# HDMI_MicroUSB.net
KiCad netlist of a schematic drawn in Altium Designer
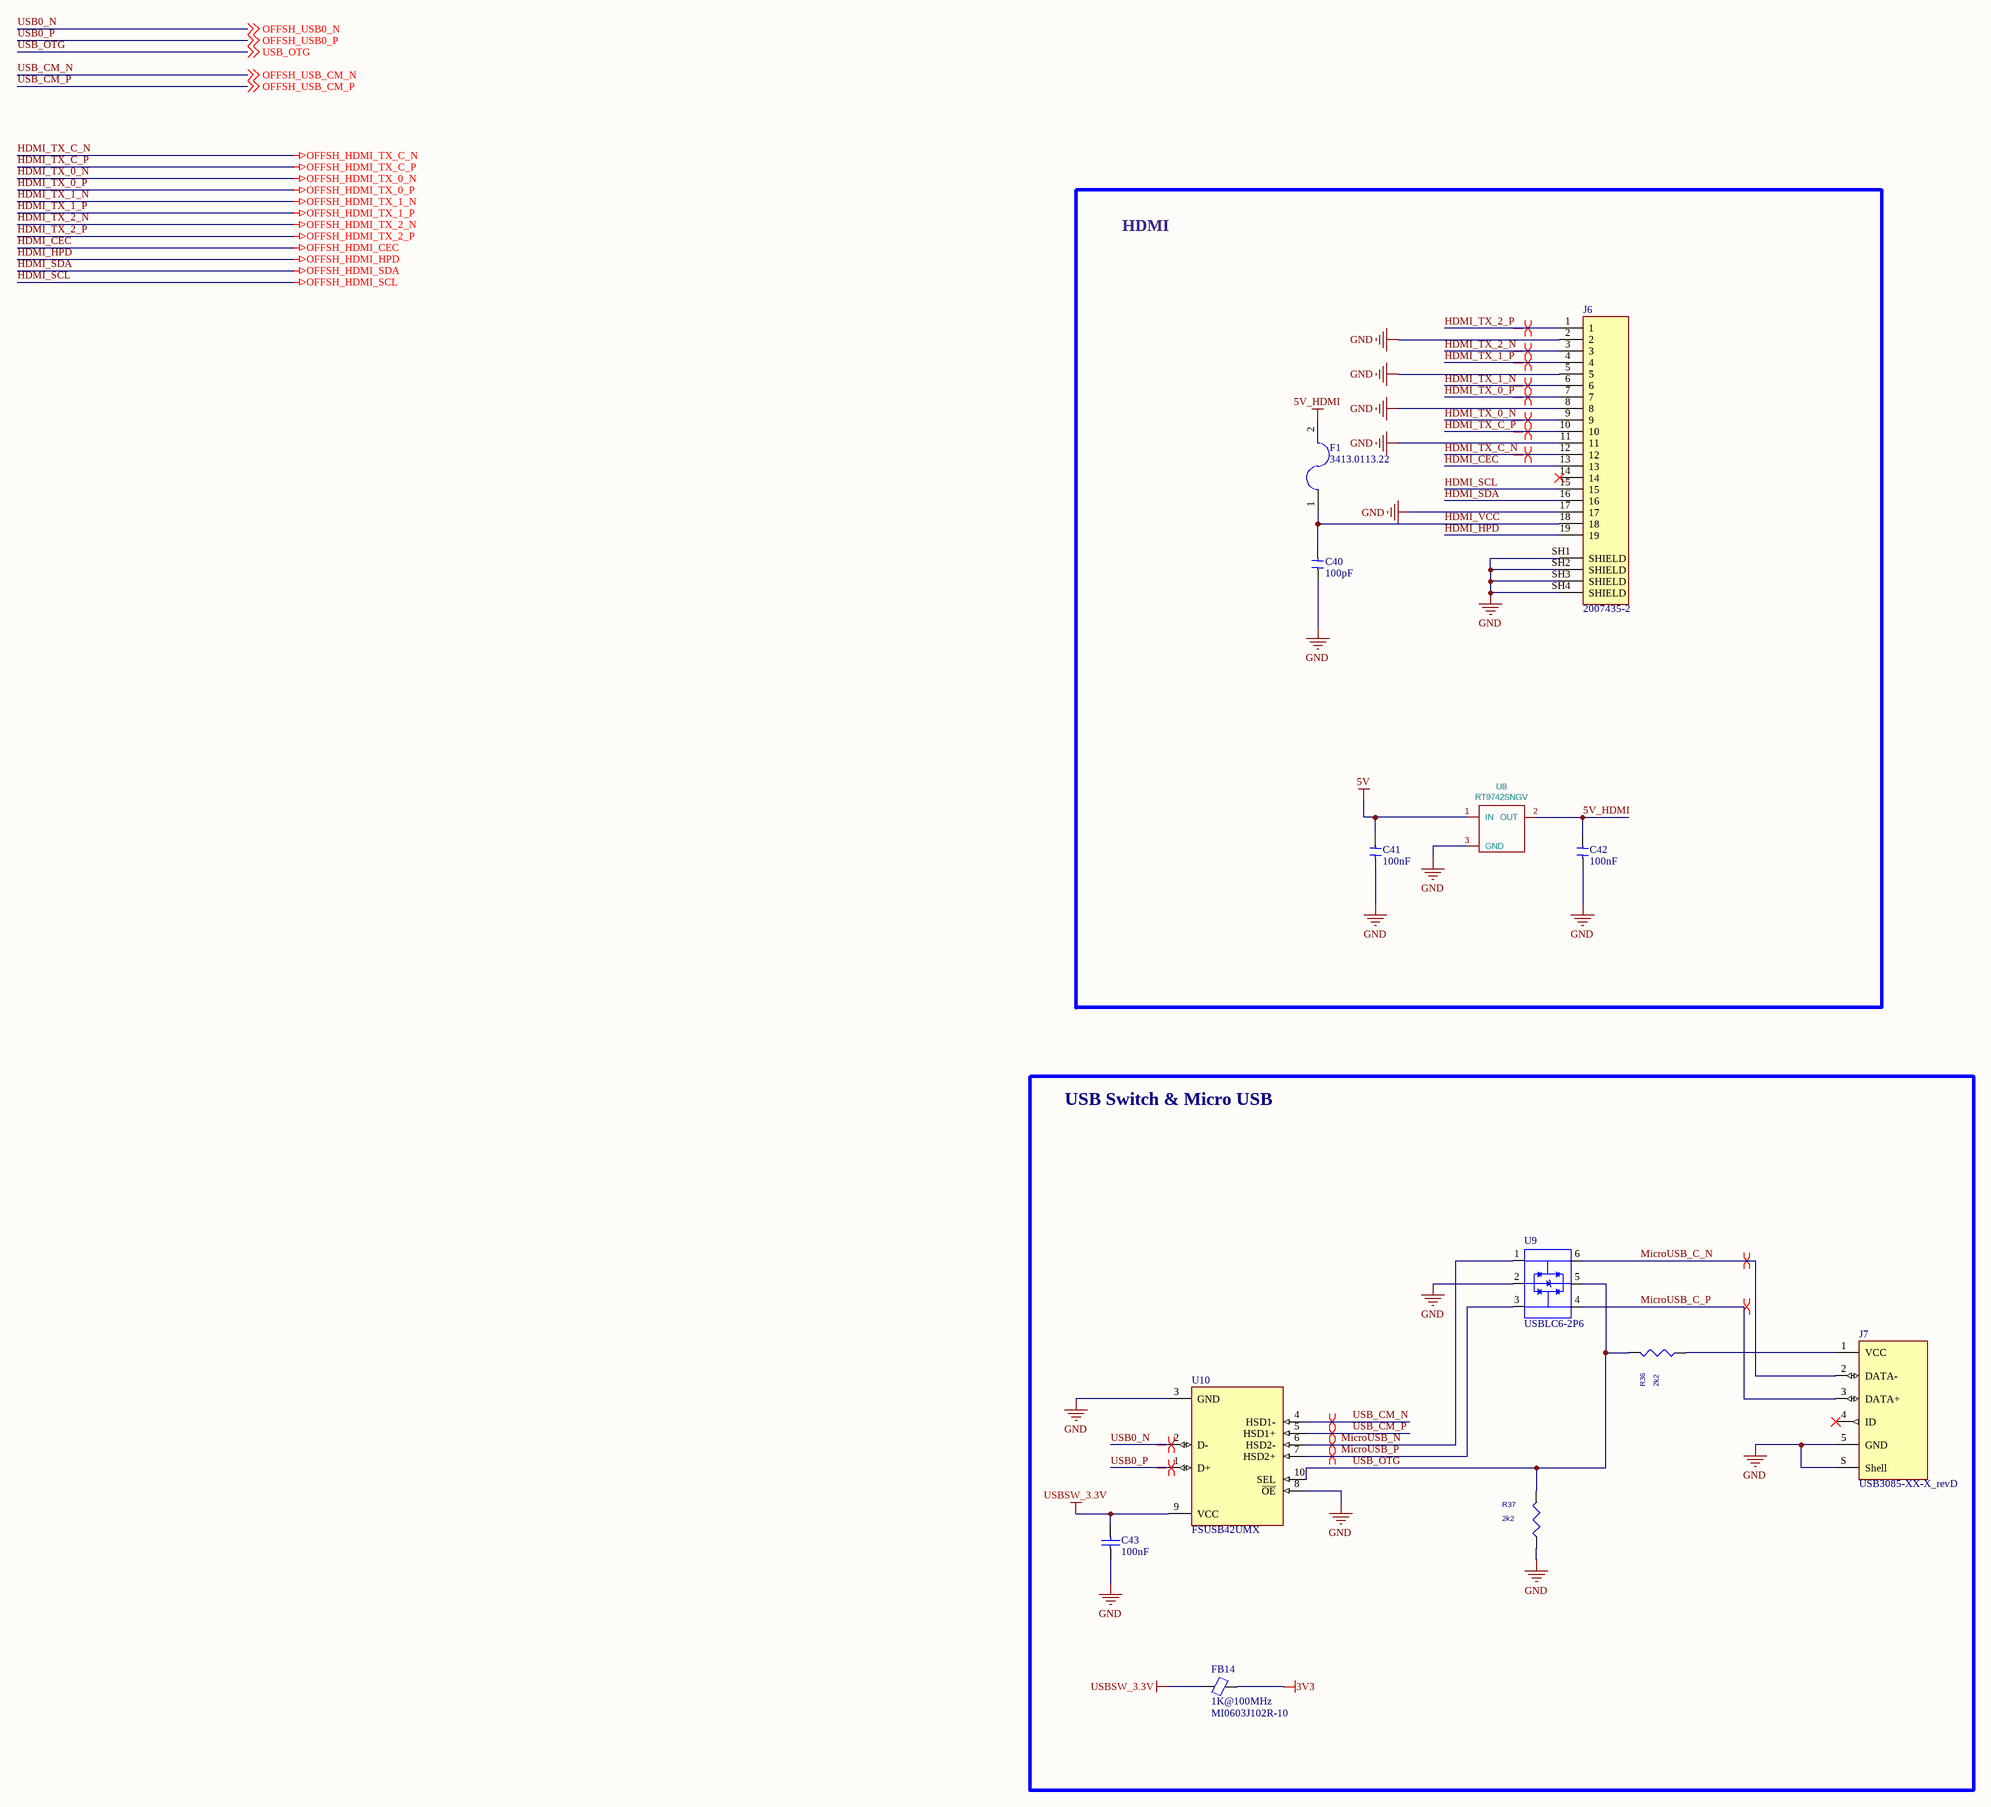
[diagram p0: HDMI_MicroUSB.SchDoc]

(export (version "E")
  (design (tool "Eeschema 10.0.6"))
  (components
    (comp (ref "C40")
      (value "100pF")
      (footprint "0603 Capacitor")
      (fields (field (name "VOLTAGE") "50v") (field (name "Comment") "Capacitor SMD"))
      (libsource (lib "SA-C7_Apr09") (part "Capacitor SMD"))
    )
    (comp (ref "C41")
      (value "100nF")
      (footprint "0603 Capacitor")
      (description "SMD capacitor")
      (fields (field (name "VOLTAGE") "50v") (field (name "Comment") "Capacitor SMD"))
      (libsource (lib "SA-C7_Apr09") (part "Capacitor SMD"))
    )
    (comp (ref "C42")
      (value "100nF")
      (footprint "0603 Capacitor")
      (fields (field (name "VOLTAGE") "50v") (field (name "Comment") "Capacitor SMD"))
      (libsource (lib "SA-C7_Apr09") (part "Capacitor SMD"))
    )
    (comp (ref "C43")
      (value "100nF")
      (footprint "CAP (0603)")
      (description "SMD capacitor")
      (fields (field (name "VOLTAGE") "50V") (field (name "Comment") "Cap"))
      (libsource (lib "SCSoft_Utils") (part "Cap"))
    )
    (comp (ref "F1")
      (value "Fuse")
      (footprint "FUSE (3413.0120.22)")
      (description "USB Host Fuse")
      (fields (field (name "PART NUMBER") "3413.0113.22"))
      (libsource (lib "SCV500_Genfare") (part "Fuse (3413.0113.22)"))
    )
    (comp (ref "FB14")
      (value "1K@100MHz")
      (footprint "FB0603")
      (description "Ferrite Bead SMD")
      (fields (field (name "PART NUMBER") "MI0603J102R-10") (field (name "Comment") "Ferrite Bead"))
      (libsource (lib "*") (part "Ferrite Bead"))
    )
    (comp (ref "J6")
      (value "2007435-2")
      (footprint "HDMI:TE_2007435-2")
      (description "Conn HDMI RCP 19 POS Solder RA Thru-Hole 19 Terminal 1 Port T/R")
      (fields (field (name "MF") "TE Connectivity"))
      (libsource (lib "2007435-2") (part "2007435-2"))
    )
    (comp (ref "J7")
      (value "USB3085-XX-X_revD")
      (footprint "USB3085-XX-X_revD")
      (description "Micro USB Receptacle, Type AB, SMT, Horizontal, Bottom Mount, without Peg")
      (libsource (lib "USB3085-30-X_revD") (part "USB3085-XX-X_revD"))
    )
    (comp (ref "R36") (value "2k2") (footprint "R0603") (libsource (lib "*") (part "RES")))
    (comp (ref "R37") (value "2k2") (footprint "R0603") (libsource (lib "*") (part "RES")))
    (comp (ref "U8") (value "RT9742SNGV") (footprint "SOT-23") (libsource (lib "CM4IO") (part "RT9742SNGV")))
    (comp (ref "U9")
      (value "USBLC6-2P6")
      (footprint "SOT50P160X60-6N")
      (description "17V Clamp 5A _8/20Âµs_ Ipp Tvs Diode Surface Mount SOT-666")
      (fields (field (name "MF") "STMicroelectronics"))
      (libsource (lib "USBLC6-2P6") (part "USBLC6-2P6"))
    )
    (comp (ref "U10")
      (value "FSUSB42UMX")
      (footprint "ON_Semiconductor_523BC_MFG")
      (description "USB Switch IC 1 Channel 10-UMLP _1.8x1.4_")
      (fields (field (name "MF") "ON Semiconductor"))
      (libsource (lib "FSUSB42UMX") (part "FSUSB42UMX"))
    )
  )
  (nets
    (net (code "1") (name "/HDMI_VCC") (class "Default")
      (node (ref "C40") (pin "1") (pintype "passive"))
      (node (ref "F1") (pin "1") (pinfunction "1_1") (pintype "passive"))
      (node (ref "J6") (pin "18") (pinfunction "18_18") (pintype "passive"))
    )
    (net (code "2") (name "/MicroUSB_C_N") (class "Default")
      (node (ref "J7") (pin "2") (pinfunction "DATA-_2") (pintype "bidirectional"))
      (node (ref "U9") (pin "6") (pinfunction "I/O1_2_6") (pintype "bidirectional"))
    )
    (net (code "3") (name "/MicroUSB_C_P") (class "Default")
      (node (ref "J7") (pin "3") (pinfunction "DATA+_3") (pintype "bidirectional"))
      (node (ref "U9") (pin "4") (pinfunction "I/O2_2_4") (pintype "bidirectional"))
    )
    (net (code "4") (name "/MicroUSB_N") (class "Default")
      (node (ref "U10") (pin "6") (pinfunction "HSD2-_6") (pintype "input"))
      (node (ref "U9") (pin "1") (pinfunction "I/O1_1_1") (pintype "bidirectional"))
    )
    (net (code "5") (name "/MicroUSB_P") (class "Default")
      (node (ref "U10") (pin "7") (pinfunction "HSD2+_7") (pintype "input"))
      (node (ref "U9") (pin "3") (pinfunction "I/O2_1_3") (pintype "bidirectional"))
    )
    (net (code "6") (name "3V3") (class "Default")
      (node (ref "FB14") (pin "2") (pinfunction "2_2") (pintype "passive"))
    )
    (net (code "7") (name "5V") (class "Default")
      (node (ref "C41") (pin "1") (pintype "passive"))
      (node (ref "U8") (pin "1") (pinfunction "IN_1") (pintype "passive"))
    )
    (net (code "8") (name "5V_HDMI") (class "Default")
      (node (ref "C42") (pin "1") (pintype "passive"))
      (node (ref "F1") (pin "2") (pinfunction "2_2") (pintype "passive"))
      (node (ref "U8") (pin "2") (pinfunction "OUT_2") (pintype "passive"))
    )
    (net (code "9") (name "GND") (class "Default")
      (node (ref "C40") (pin "2") (pintype "passive"))
      (node (ref "C41") (pin "2") (pintype "passive"))
      (node (ref "C42") (pin "2") (pintype "passive"))
      (node (ref "C43") (pin "1") (pinfunction "1_1") (pintype "passive"))
      (node (ref "J6") (pin "11") (pinfunction "11_11") (pintype "passive"))
      (node (ref "J6") (pin "17") (pinfunction "17_17") (pintype "passive"))
      (node (ref "J6") (pin "2") (pinfunction "2_2") (pintype "passive"))
      (node (ref "J6") (pin "5") (pinfunction "5_5") (pintype "passive"))
      (node (ref "J6") (pin "8") (pinfunction "8_8") (pintype "passive"))
      (node (ref "J6") (pin "SH1") (pinfunction "SHIELD_SH1") (pintype "passive"))
      (node (ref "J6") (pin "SH2") (pinfunction "SHIELD_SH2") (pintype "passive"))
      (node (ref "J6") (pin "SH3") (pinfunction "SHIELD_SH3") (pintype "passive"))
      (node (ref "J6") (pin "SH4") (pinfunction "SHIELD_SH4") (pintype "passive"))
      (node (ref "J7") (pin "5") (pinfunction "GND_5") (pintype "power_in"))
      (node (ref "J7") (pin "S") (pinfunction "Shell_S") (pintype "power_in"))
      (node (ref "R37") (pin "2") (pinfunction "2_2") (pintype "passive"))
      (node (ref "U10") (pin "3") (pinfunction "GND_3") (pintype "power_in"))
      (node (ref "U10") (pin "8") (pinfunction "~{OE}_8") (pintype "input"))
      (node (ref "U8") (pin "3") (pinfunction "GND_3") (pintype "passive"))
      (node (ref "U9") (pin "2") (pinfunction "GND_2") (pintype "power_in"))
    )
    (net (code "10") (name "Net-(J7-VCC)") (class "Default")
      (node (ref "J7") (pin "1") (pinfunction "VCC_1") (pintype "power_in"))
      (node (ref "R36") (pin "2") (pinfunction "2_2") (pintype "passive"))
    )
    (net (code "11") (name "OFFSH_HDMI_CEC") (class "Default")
      (node (ref "J6") (pin "13") (pinfunction "13_13") (pintype "passive"))
    )
    (net (code "12") (name "OFFSH_HDMI_HPD") (class "Default")
      (node (ref "J6") (pin "19") (pinfunction "19_19") (pintype "passive"))
    )
    (net (code "13") (name "OFFSH_HDMI_SCL") (class "Default")
      (node (ref "J6") (pin "15") (pinfunction "15_15") (pintype "passive"))
    )
    (net (code "14") (name "OFFSH_HDMI_SDA") (class "Default")
      (node (ref "J6") (pin "16") (pinfunction "16_16") (pintype "passive"))
    )
    (net (code "15") (name "OFFSH_HDMI_TX_0_N") (class "Default")
      (node (ref "J6") (pin "9") (pinfunction "9_9") (pintype "passive"))
    )
    (net (code "16") (name "OFFSH_HDMI_TX_0_P") (class "Default")
      (node (ref "J6") (pin "7") (pinfunction "7_7") (pintype "passive"))
    )
    (net (code "17") (name "OFFSH_HDMI_TX_1_N") (class "Default")
      (node (ref "J6") (pin "6") (pinfunction "6_6") (pintype "passive"))
    )
    (net (code "18") (name "OFFSH_HDMI_TX_1_P") (class "Default")
      (node (ref "J6") (pin "4") (pinfunction "4_4") (pintype "passive"))
    )
    (net (code "19") (name "OFFSH_HDMI_TX_2_N") (class "Default")
      (node (ref "J6") (pin "3") (pinfunction "3_3") (pintype "passive"))
    )
    (net (code "20") (name "OFFSH_HDMI_TX_2_P") (class "Default")
      (node (ref "J6") (pin "1") (pinfunction "1_1") (pintype "passive"))
    )
    (net (code "21") (name "OFFSH_HDMI_TX_C_N") (class "Default")
      (node (ref "J6") (pin "12") (pinfunction "12_12") (pintype "passive"))
    )
    (net (code "22") (name "OFFSH_HDMI_TX_C_P") (class "Default")
      (node (ref "J6") (pin "10") (pinfunction "10_10") (pintype "passive"))
    )
    (net (code "23") (name "OFFSH_USB0_N") (class "Default")
      (node (ref "U10") (pin "2") (pinfunction "D-_2") (pintype "bidirectional"))
    )
    (net (code "24") (name "OFFSH_USB0_P") (class "Default")
      (node (ref "U10") (pin "1") (pinfunction "D+_1") (pintype "bidirectional"))
    )
    (net (code "25") (name "OFFSH_USB_CM_N") (class "Default")
      (node (ref "U10") (pin "4") (pinfunction "HSD1-_4") (pintype "input"))
    )
    (net (code "26") (name "OFFSH_USB_CM_P") (class "Default")
      (node (ref "U10") (pin "5") (pinfunction "HSD1+_5") (pintype "input"))
    )
    (net (code "27") (name "USBSW_3.3V") (class "Default")
      (node (ref "C43") (pin "2") (pinfunction "2_2") (pintype "passive"))
      (node (ref "FB14") (pin "1") (pinfunction "1_1") (pintype "passive"))
      (node (ref "U10") (pin "9") (pinfunction "VCC_9") (pintype "power_in"))
    )
    (net (code "28") (name "USB_OTG") (class "Default")
      (node (ref "R36") (pin "1") (pinfunction "1_1") (pintype "passive"))
      (node (ref "R37") (pin "1") (pinfunction "1_1") (pintype "passive"))
      (node (ref "U10") (pin "10") (pinfunction "SEL_10") (pintype "input"))
      (node (ref "U9") (pin "5") (pinfunction "VBUS_5") (pintype "power_in"))
    )
    (net (code "29") (name "unconnected-(J6-Pad14)") (class "Default")
      (node (ref "J6") (pin "14") (pinfunction "14_14") (pintype "passive+no_connect"))
    )
    (net (code "30") (name "unconnected-(J7-ID-Pad4)") (class "Default")
      (node (ref "J7") (pin "4") (pinfunction "ID_4") (pintype "output+no_connect"))
    )
  )
)
